# LB_BIT_o9_BARGRAPH-v02_rev1.net
KiCad netlist of a schematic drawn in EAGLE
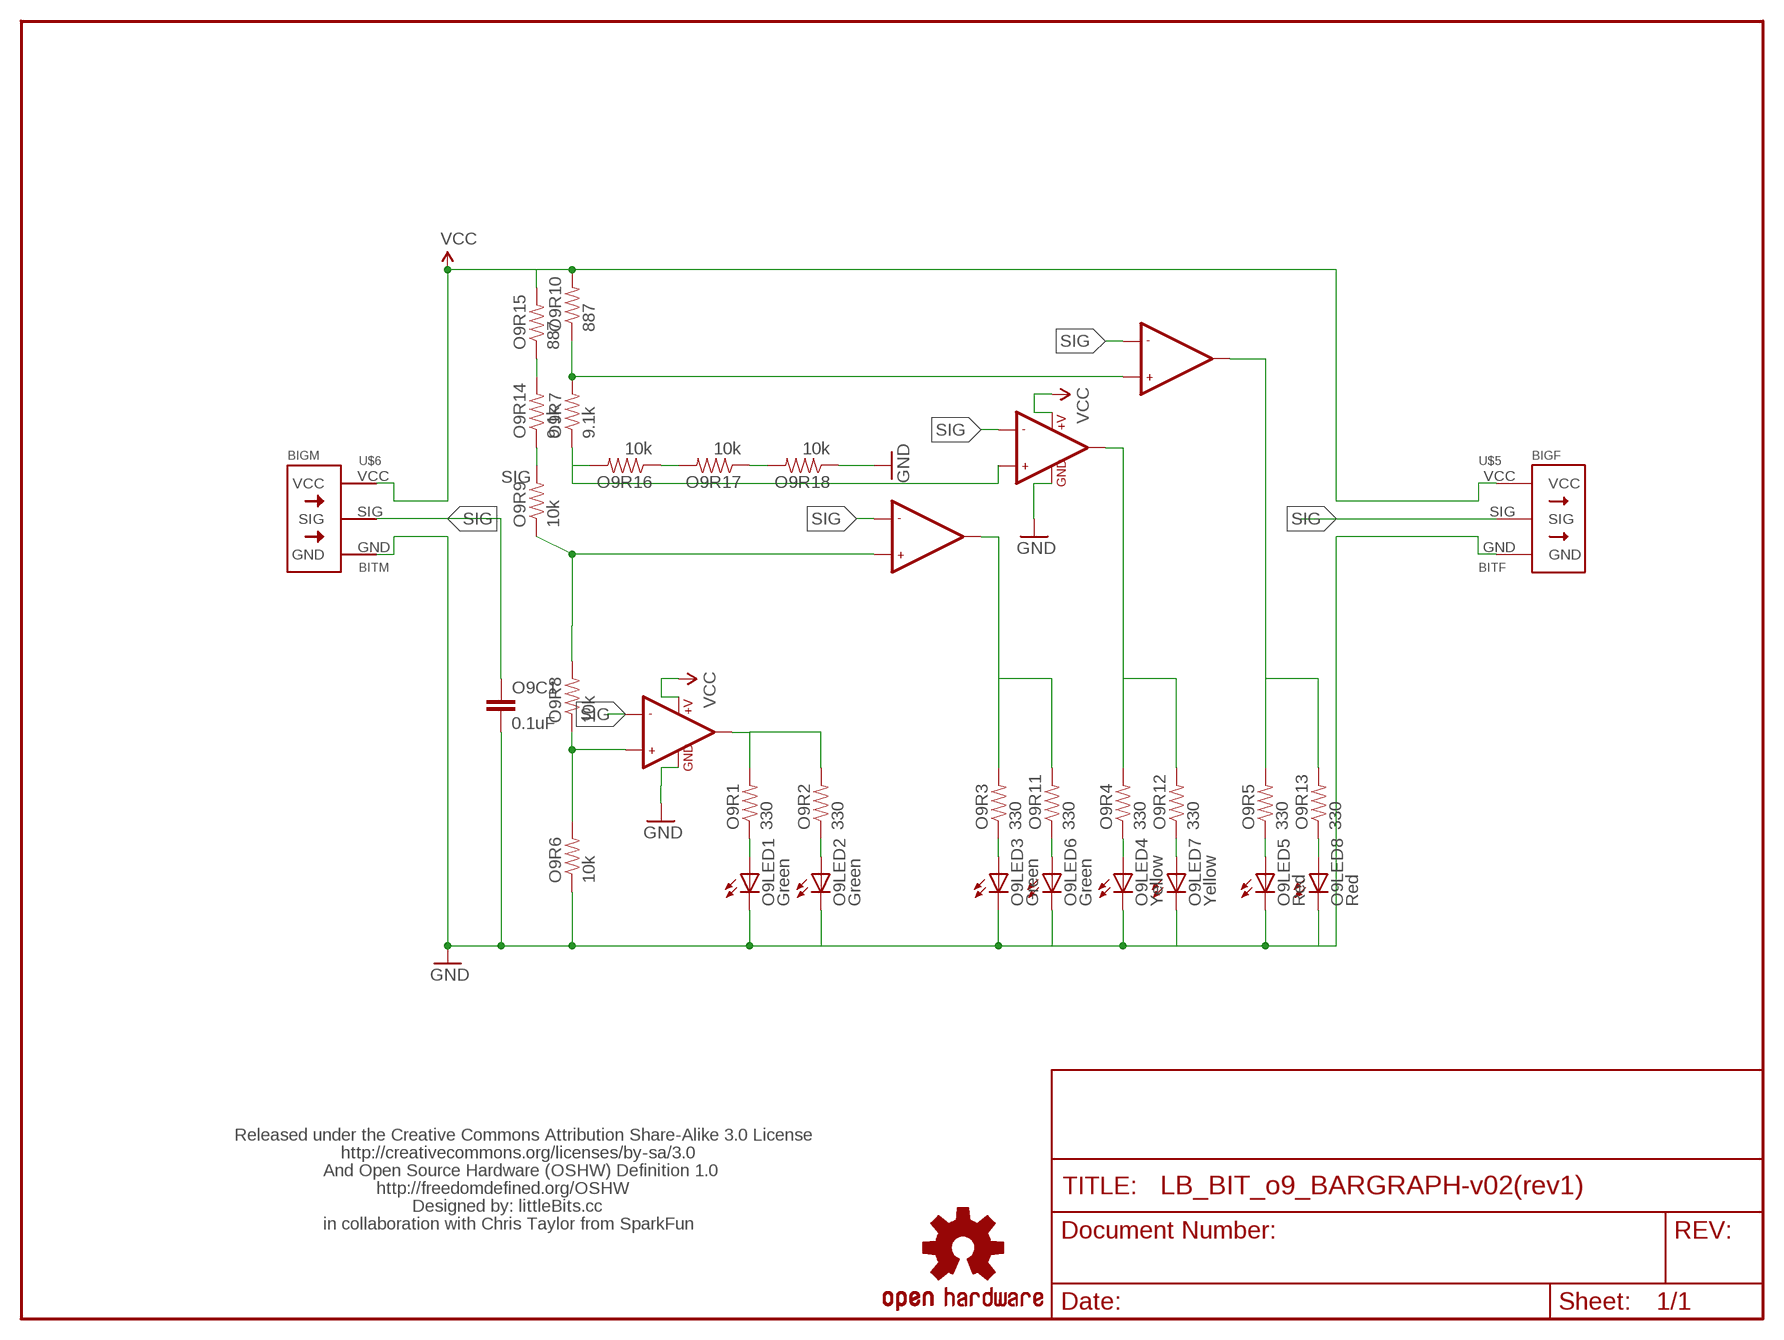
[diagram p0: schematic, sheet 1]

(export (version "E")
  (design (tool "Eeschema 10.0.6"))
  (components
    (comp (ref "O9C1")
      (value "0.1uF")
      (footprint "eagle-import:0603-CAP")
      (libsource (lib "eagle-import") (part "CAP0603-CAP"))
    )
    (comp (ref "O9LED1")
      (value "Green")
      (footprint "eagle-import:LED-1206")
      (libsource (lib "eagle-import") (part "LED1206"))
    )
    (comp (ref "O9LED2")
      (value "Green")
      (footprint "eagle-import:LED-1206")
      (libsource (lib "eagle-import") (part "LED1206"))
    )
    (comp (ref "O9LED3")
      (value "Green")
      (footprint "eagle-import:LED-1206")
      (libsource (lib "eagle-import") (part "LED1206"))
    )
    (comp (ref "O9LED4")
      (value "Yellow")
      (footprint "eagle-import:LED-1206")
      (libsource (lib "eagle-import") (part "LED1206"))
    )
    (comp (ref "O9LED5")
      (value "Red")
      (footprint "eagle-import:LED-1206")
      (libsource (lib "eagle-import") (part "LED1206"))
    )
    (comp (ref "O9LED6")
      (value "Green")
      (footprint "eagle-import:LED-1206")
      (libsource (lib "eagle-import") (part "LED1206"))
    )
    (comp (ref "O9LED7")
      (value "Yellow")
      (footprint "eagle-import:LED-1206")
      (libsource (lib "eagle-import") (part "LED1206"))
    )
    (comp (ref "O9LED8")
      (value "Red")
      (footprint "eagle-import:LED-1206")
      (libsource (lib "eagle-import") (part "LED1206"))
    )
    (comp (ref "O9R1")
      (value "330")
      (footprint "eagle-import:0805")
      (libsource (lib "eagle-import") (part "RESISTOR"))
    )
    (comp (ref "O9R2")
      (value "330")
      (footprint "eagle-import:0805")
      (libsource (lib "eagle-import") (part "RESISTOR"))
    )
    (comp (ref "O9R3")
      (value "330")
      (footprint "eagle-import:0805")
      (libsource (lib "eagle-import") (part "RESISTOR"))
    )
    (comp (ref "O9R4")
      (value "330")
      (footprint "eagle-import:0805")
      (libsource (lib "eagle-import") (part "RESISTOR"))
    )
    (comp (ref "O9R5")
      (value "330")
      (footprint "eagle-import:0805")
      (libsource (lib "eagle-import") (part "RESISTOR"))
    )
    (comp (ref "O9R6")
      (value "10k")
      (footprint "eagle-import:0805")
      (libsource (lib "eagle-import") (part "RESISTOR"))
    )
    (comp (ref "O9R7")
      (value "9.1k")
      (footprint "eagle-import:0805")
      (libsource (lib "eagle-import") (part "RESISTOR"))
    )
    (comp (ref "O9R8")
      (value "10k")
      (footprint "eagle-import:0805")
      (libsource (lib "eagle-import") (part "RESISTOR"))
    )
    (comp (ref "O9R9")
      (value "10k")
      (footprint "eagle-import:0805")
      (libsource (lib "eagle-import") (part "RESISTOR"))
    )
    (comp (ref "O9R10")
      (value "887")
      (footprint "eagle-import:0805")
      (libsource (lib "eagle-import") (part "RESISTOR"))
    )
    (comp (ref "O9R11")
      (value "330")
      (footprint "eagle-import:0805")
      (libsource (lib "eagle-import") (part "RESISTOR"))
    )
    (comp (ref "O9R12")
      (value "330")
      (footprint "eagle-import:0805")
      (libsource (lib "eagle-import") (part "RESISTOR"))
    )
    (comp (ref "O9R13")
      (value "330")
      (footprint "eagle-import:0805")
      (libsource (lib "eagle-import") (part "RESISTOR"))
    )
    (comp (ref "O9R14")
      (value "9.1k")
      (footprint "eagle-import:0805")
      (libsource (lib "eagle-import") (part "RESISTOR"))
    )
    (comp (ref "O9R15")
      (value "887")
      (footprint "eagle-import:0805")
      (libsource (lib "eagle-import") (part "RESISTOR"))
    )
    (comp (ref "O9R16")
      (value "10k")
      (footprint "eagle-import:0805")
      (libsource (lib "eagle-import") (part "RESISTOR"))
    )
    (comp (ref "O9R17")
      (value "10k")
      (footprint "eagle-import:0805")
      (libsource (lib "eagle-import") (part "RESISTOR"))
    )
    (comp (ref "O9R18")
      (value "10k")
      (footprint "eagle-import:0805")
      (libsource (lib "eagle-import") (part "RESISTOR"))
    )
    (comp (ref "U$1")
      (value "LB_CREDITS")
      (footprint "eagle-import:OSHWCREDIT")
      (libsource (lib "eagle-import") (part "LB_CREDITS"))
    )
    (comp (ref "U$2")
      (value "LMV358")
      (footprint "eagle-import:SO08")
      (libsource (lib "eagle-import") (part "LMV358"))
    )
    (comp (ref "U$3")
      (value "OSHW-LOGOL")
      (footprint "eagle-import:OSHW-LOGO-L")
      (libsource (lib "eagle-import") (part "OSHW-LOGOL"))
    )
    (comp (ref "U$4")
      (value "LMV358")
      (footprint "eagle-import:SO08")
      (libsource (lib "eagle-import") (part "LMV358"))
    )
    (comp (ref "U$5")
      (value "BITF")
      (footprint "eagle-import:BITM")
      (libsource (lib "eagle-import") (part "BITF"))
    )
    (comp (ref "U$6")
      (value "BITM")
      (footprint "eagle-import:BITM")
      (libsource (lib "eagle-import") (part "BITM"))
    )
  )
  (nets
    (net (code "1") (name "GND") (class "Default")
      (node (ref "O9C1") (pin "2") (pinfunction "2_2") (pintype "passive"))
      (node (ref "O9LED1") (pin "C") (pinfunction "C_C") (pintype "passive"))
      (node (ref "O9LED2") (pin "C") (pinfunction "C_C") (pintype "passive"))
      (node (ref "O9LED3") (pin "C") (pinfunction "C_C") (pintype "passive"))
      (node (ref "O9LED4") (pin "C") (pinfunction "C_C") (pintype "passive"))
      (node (ref "O9LED5") (pin "C") (pinfunction "C_C") (pintype "passive"))
      (node (ref "O9LED6") (pin "C") (pinfunction "C_C") (pintype "passive"))
      (node (ref "O9LED7") (pin "C") (pinfunction "C_C") (pintype "passive"))
      (node (ref "O9LED8") (pin "C") (pinfunction "C_C") (pintype "passive"))
      (node (ref "O9R18") (pin "1") (pinfunction "1_1") (pintype "passive"))
      (node (ref "O9R6") (pin "1") (pinfunction "1_1") (pintype "passive"))
      (node (ref "U$2") (pin "4") (pinfunction "GND_4") (pintype "power_in"))
      (node (ref "U$4") (pin "4") (pinfunction "GND_4") (pintype "power_in"))
      (node (ref "U$5") (pin "GND") (pinfunction "GND_GND") (pintype "bidirectional"))
      (node (ref "U$6") (pin "GND") (pinfunction "GND_GND") (pintype "bidirectional"))
    )
    (net (code "2") (name "Net-(O9LED1-PadA)") (class "Default")
      (node (ref "O9LED1") (pin "A") (pinfunction "A_A") (pintype "passive"))
      (node (ref "O9R1") (pin "1") (pinfunction "1_1") (pintype "passive"))
    )
    (net (code "3") (name "Net-(O9LED2-PadA)") (class "Default")
      (node (ref "O9LED2") (pin "A") (pinfunction "A_A") (pintype "passive"))
      (node (ref "O9R2") (pin "1") (pinfunction "1_1") (pintype "passive"))
    )
    (net (code "4") (name "Net-(O9LED3-PadA)") (class "Default")
      (node (ref "O9LED3") (pin "A") (pinfunction "A_A") (pintype "passive"))
      (node (ref "O9R3") (pin "1") (pinfunction "1_1") (pintype "passive"))
    )
    (net (code "5") (name "Net-(O9LED4-PadA)") (class "Default")
      (node (ref "O9LED4") (pin "A") (pinfunction "A_A") (pintype "passive"))
      (node (ref "O9R4") (pin "1") (pinfunction "1_1") (pintype "passive"))
    )
    (net (code "6") (name "Net-(O9LED5-PadA)") (class "Default")
      (node (ref "O9LED5") (pin "A") (pinfunction "A_A") (pintype "passive"))
      (node (ref "O9R5") (pin "1") (pinfunction "1_1") (pintype "passive"))
    )
    (net (code "7") (name "Net-(O9LED6-PadA)") (class "Default")
      (node (ref "O9LED6") (pin "A") (pinfunction "A_A") (pintype "passive"))
      (node (ref "O9R11") (pin "1") (pinfunction "1_1") (pintype "passive"))
    )
    (net (code "8") (name "Net-(O9LED7-PadA)") (class "Default")
      (node (ref "O9LED7") (pin "A") (pinfunction "A_A") (pintype "passive"))
      (node (ref "O9R12") (pin "1") (pinfunction "1_1") (pintype "passive"))
    )
    (net (code "9") (name "Net-(O9LED8-PadA)") (class "Default")
      (node (ref "O9LED8") (pin "A") (pinfunction "A_A") (pintype "passive"))
      (node (ref "O9R13") (pin "1") (pinfunction "1_1") (pintype "passive"))
    )
    (net (code "10") (name "Net-(O9R14-Pad1)") (class "Default")
      (node (ref "O9R14") (pin "1") (pinfunction "1_1") (pintype "passive"))
      (node (ref "O9R9") (pin "2") (pinfunction "2_2") (pintype "passive"))
    )
    (net (code "11") (name "Net-(O9R14-Pad2)") (class "Default")
      (node (ref "O9R14") (pin "2") (pinfunction "2_2") (pintype "passive"))
      (node (ref "O9R15") (pin "1") (pinfunction "1_1") (pintype "passive"))
    )
    (net (code "12") (name "Net-(O9R16-Pad1)") (class "Default")
      (node (ref "O9R16") (pin "1") (pinfunction "1_1") (pintype "passive"))
      (node (ref "O9R17") (pin "2") (pinfunction "2_2") (pintype "passive"))
    )
    (net (code "13") (name "Net-(O9R17-Pad1)") (class "Default")
      (node (ref "O9R17") (pin "1") (pinfunction "1_1") (pintype "passive"))
      (node (ref "O9R18") (pin "2") (pinfunction "2_2") (pintype "passive"))
    )
    (net (code "14") (name "Net-(U$2A-+IN1)") (class "Default")
      (node (ref "O9R6") (pin "2") (pinfunction "2_2") (pintype "passive"))
      (node (ref "O9R8") (pin "1") (pinfunction "1_1") (pintype "passive"))
      (node (ref "U$2") (pin "3") (pinfunction "+IN1_3") (pintype "input"))
    )
    (net (code "15") (name "Net-(U$2A-OUT1)") (class "Default")
      (node (ref "O9R1") (pin "2") (pinfunction "2_2") (pintype "passive"))
      (node (ref "O9R2") (pin "2") (pinfunction "2_2") (pintype "passive"))
      (node (ref "U$2") (pin "1") (pinfunction "OUT1_1") (pintype "output"))
    )
    (net (code "16") (name "Net-(U$2B-+IN2)") (class "Default")
      (node (ref "O9R8") (pin "2") (pinfunction "2_2") (pintype "passive"))
      (node (ref "O9R9") (pin "1") (pinfunction "1_1") (pintype "passive"))
      (node (ref "U$2") (pin "5") (pinfunction "+IN2_5") (pintype "input"))
    )
    (net (code "17") (name "Net-(U$2B-OUT2)") (class "Default")
      (node (ref "O9R11") (pin "2") (pinfunction "2_2") (pintype "passive"))
      (node (ref "O9R3") (pin "2") (pinfunction "2_2") (pintype "passive"))
      (node (ref "U$2") (pin "7") (pinfunction "OUT2_7") (pintype "output"))
    )
    (net (code "18") (name "Net-(U$4A-+IN1)") (class "Default")
      (node (ref "O9R16") (pin "2") (pinfunction "2_2") (pintype "passive"))
      (node (ref "O9R7") (pin "1") (pinfunction "1_1") (pintype "passive"))
      (node (ref "U$4") (pin "3") (pinfunction "+IN1_3") (pintype "input"))
    )
    (net (code "19") (name "Net-(U$4A-OUT1)") (class "Default")
      (node (ref "O9R12") (pin "2") (pinfunction "2_2") (pintype "passive"))
      (node (ref "O9R4") (pin "2") (pinfunction "2_2") (pintype "passive"))
      (node (ref "U$4") (pin "1") (pinfunction "OUT1_1") (pintype "output"))
    )
    (net (code "20") (name "Net-(U$4B-+IN2)") (class "Default")
      (node (ref "O9R10") (pin "1") (pinfunction "1_1") (pintype "passive"))
      (node (ref "O9R7") (pin "2") (pinfunction "2_2") (pintype "passive"))
      (node (ref "U$4") (pin "5") (pinfunction "+IN2_5") (pintype "input"))
    )
    (net (code "21") (name "Net-(U$4B-OUT2)") (class "Default")
      (node (ref "O9R13") (pin "2") (pinfunction "2_2") (pintype "passive"))
      (node (ref "O9R5") (pin "2") (pinfunction "2_2") (pintype "passive"))
      (node (ref "U$4") (pin "7") (pinfunction "OUT2_7") (pintype "output"))
    )
    (net (code "22") (name "SIG") (class "Default")
      (node (ref "O9C1") (pin "1") (pinfunction "1_1") (pintype "passive"))
      (node (ref "U$2") (pin "2") (pinfunction "-IN1_2") (pintype "input"))
      (node (ref "U$2") (pin "6") (pinfunction "-IN2_6") (pintype "input"))
      (node (ref "U$4") (pin "2") (pinfunction "-IN1_2") (pintype "input"))
      (node (ref "U$4") (pin "6") (pinfunction "-IN2_6") (pintype "input"))
      (node (ref "U$5") (pin "SIG") (pinfunction "SIG_SIG") (pintype "bidirectional"))
      (node (ref "U$6") (pin "SIG") (pinfunction "SIG_SIG") (pintype "bidirectional"))
    )
    (net (code "23") (name "VCC") (class "Default")
      (node (ref "O9R10") (pin "2") (pinfunction "2_2") (pintype "passive"))
      (node (ref "O9R15") (pin "2") (pinfunction "2_2") (pintype "passive"))
      (node (ref "U$2") (pin "8") (pinfunction "+V_8") (pintype "power_in"))
      (node (ref "U$4") (pin "8") (pinfunction "+V_8") (pintype "power_in"))
      (node (ref "U$5") (pin "VCC") (pinfunction "VCC_VCC") (pintype "bidirectional"))
      (node (ref "U$6") (pin "VCC") (pinfunction "VCC_VCC") (pintype "bidirectional"))
    )
  )
)
